# boardV4.net
KiCad netlist of a schematic drawn in EAGLE
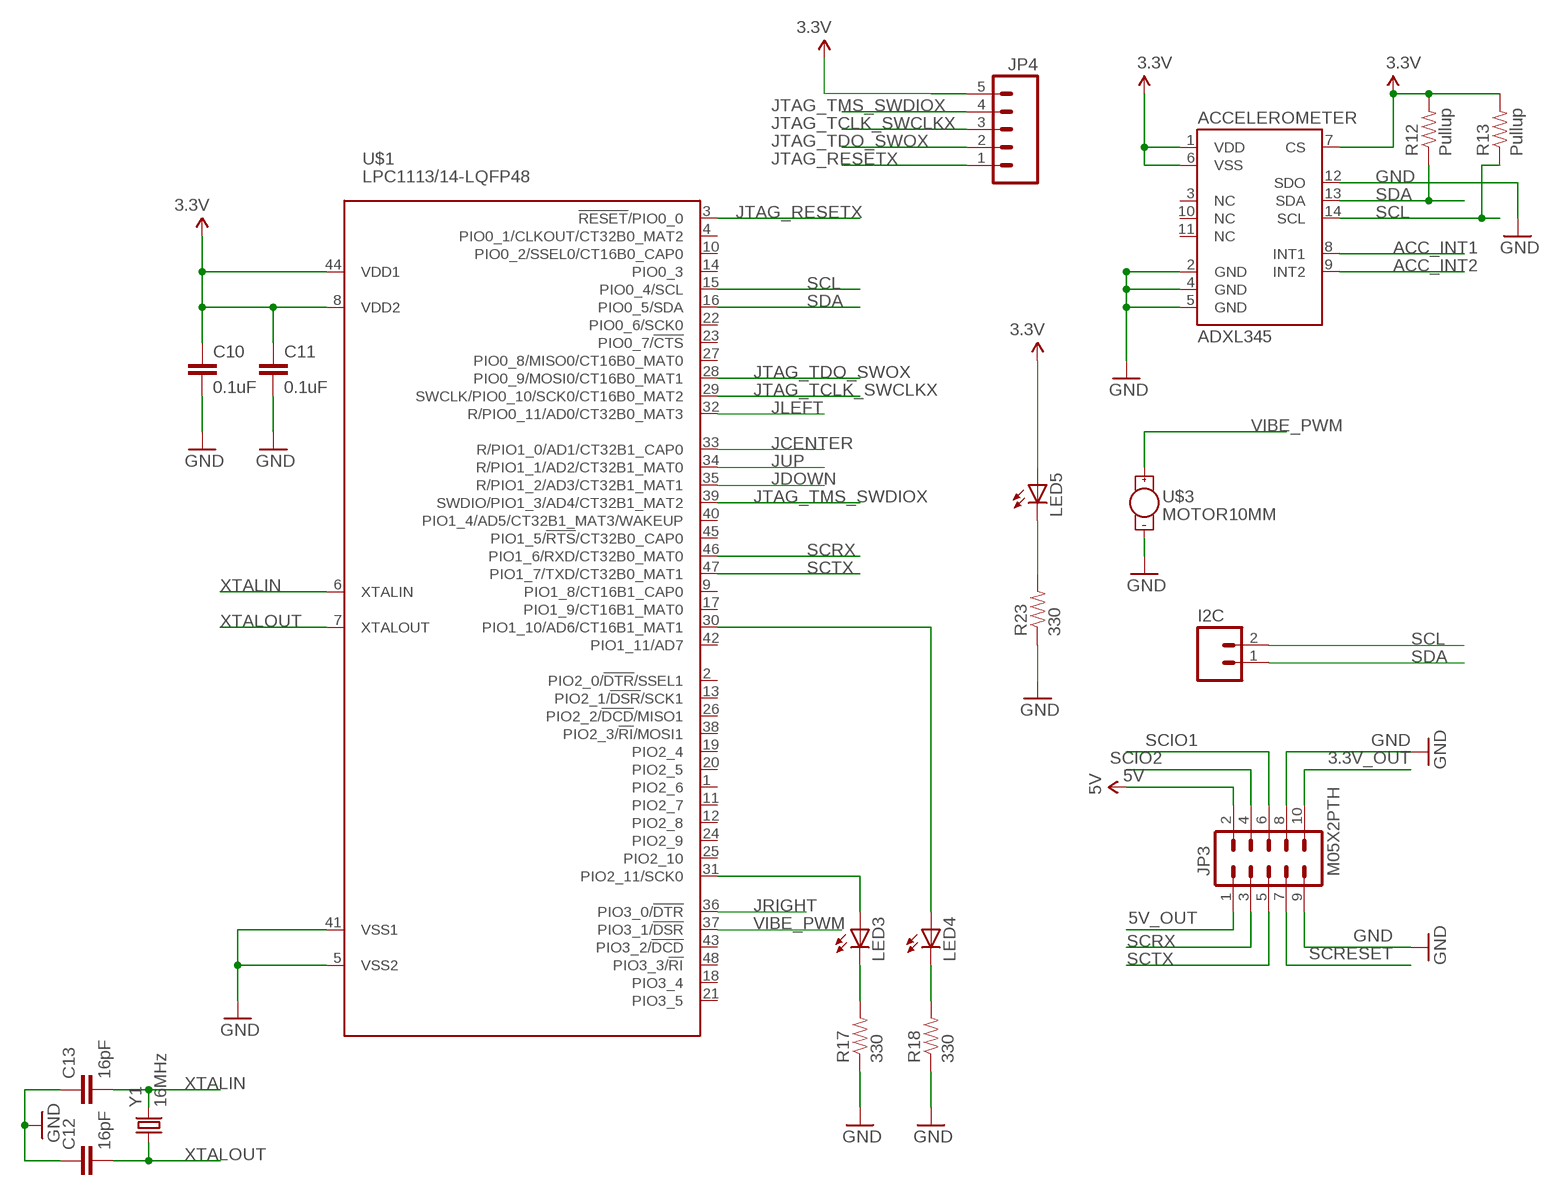
[diagram p0: schematic, sheet 1]
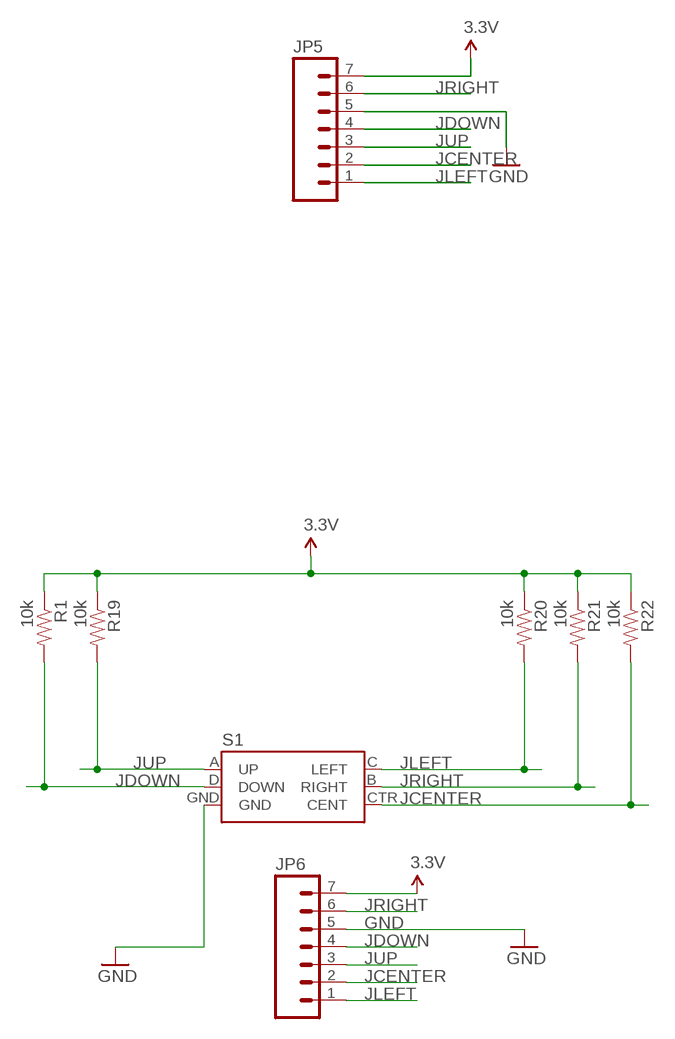
[diagram p1: schematic, sheet 2]
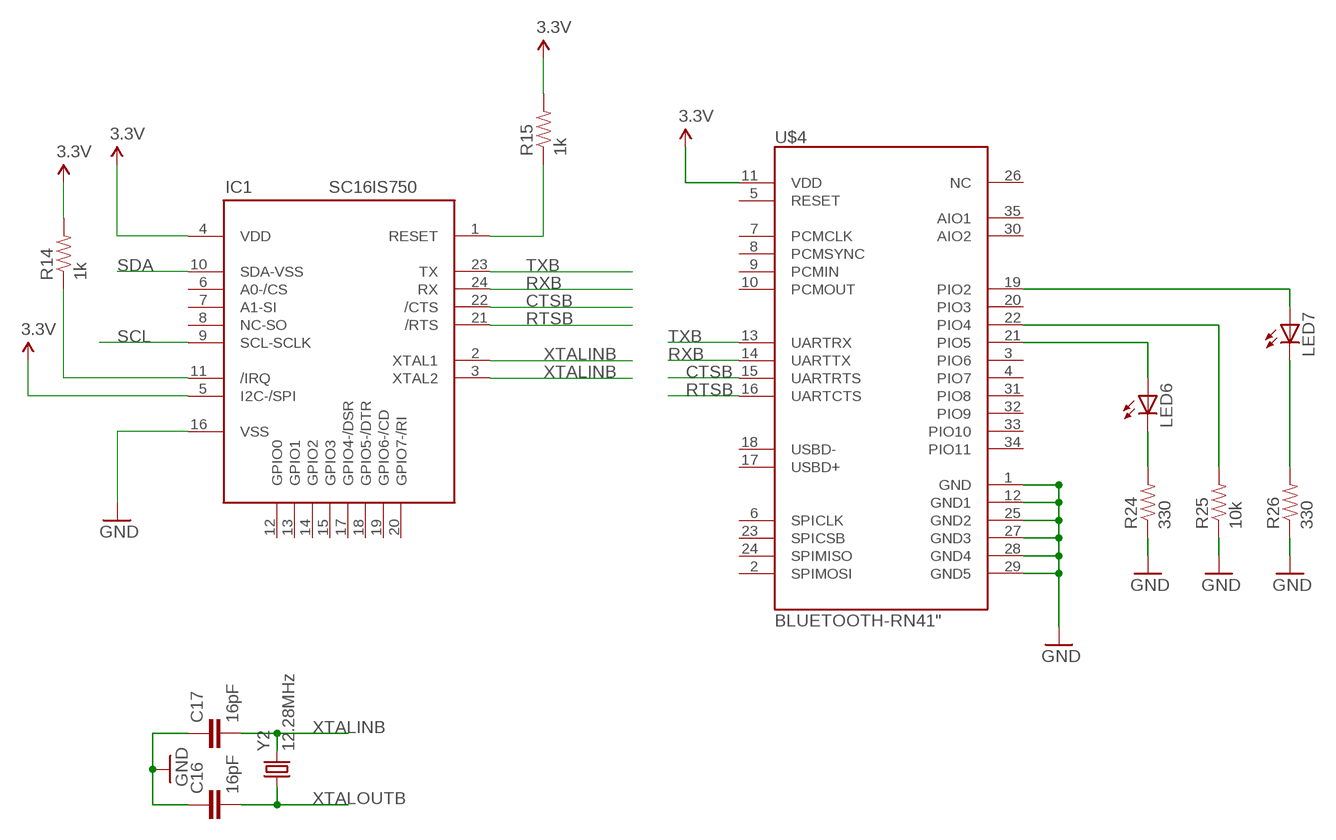
[diagram p2: schematic, sheet 3]
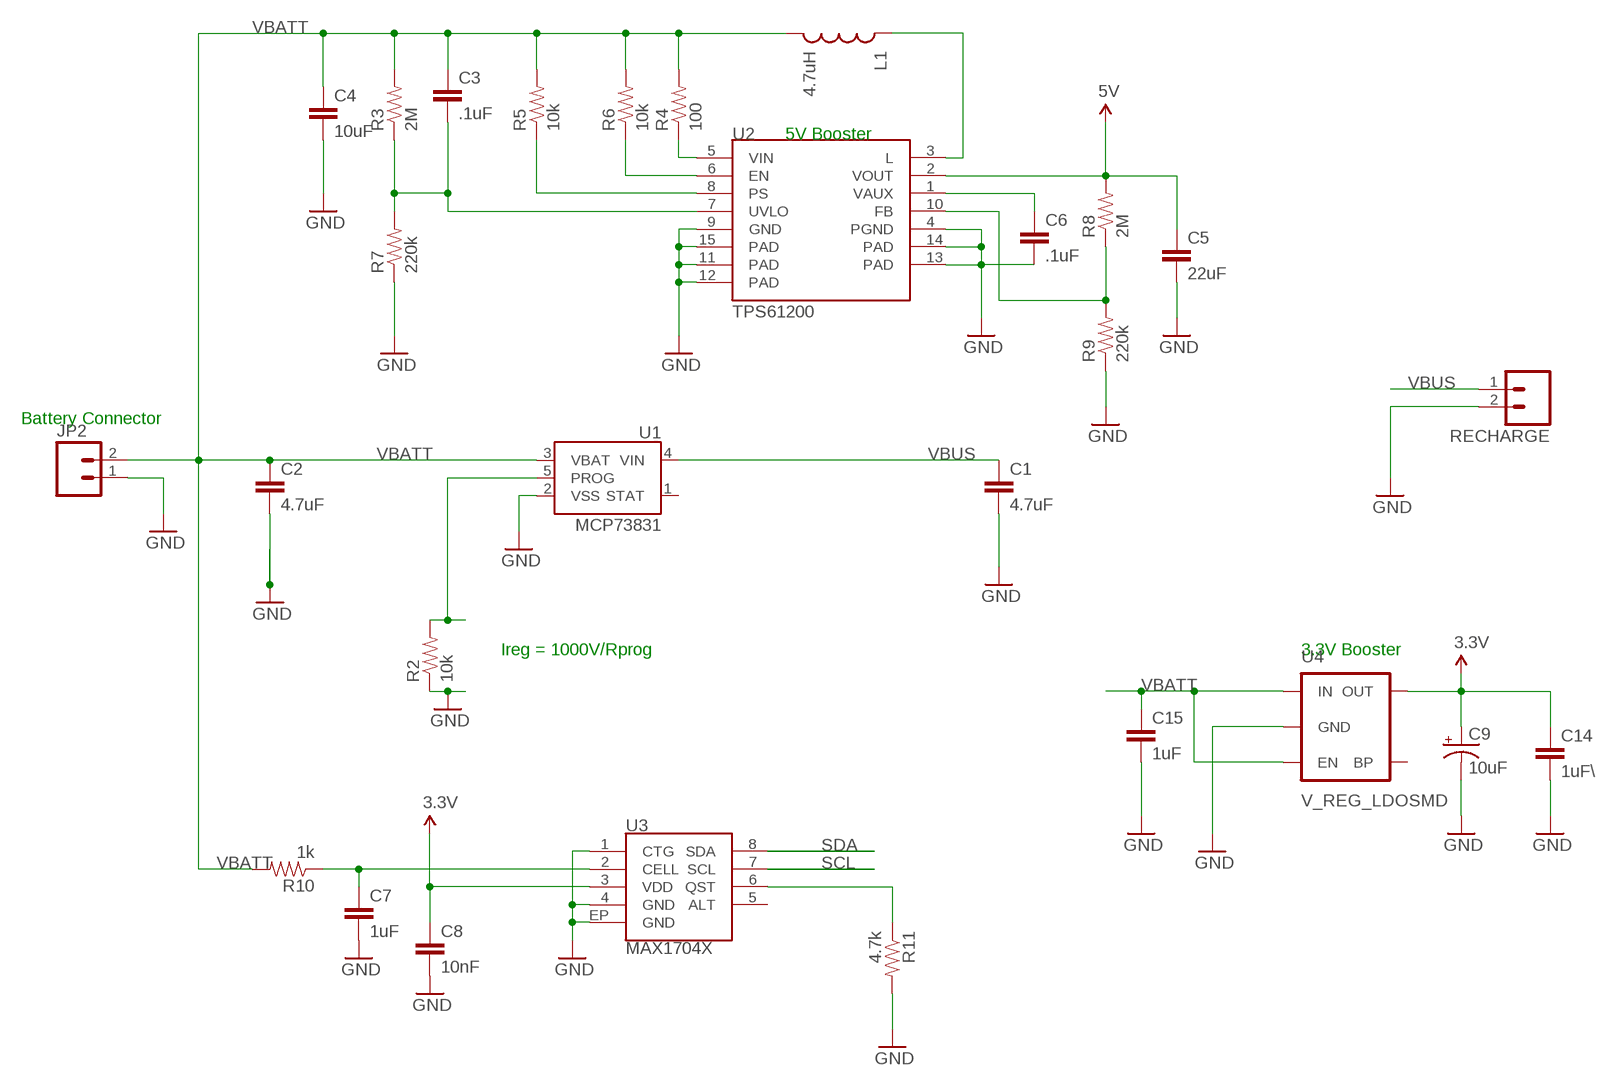
[diagram p3: schematic, sheet 4]

(export (version "E")
  (design (tool "Eeschema 10.0.6"))
  (components
    (comp (ref "C16")
      (value "16pF")
      (footprint "eagle-import:0603-CAP")
      (libsource (lib "eagle-import") (part "CAP0603-CAP"))
    )
    (comp (ref "C17")
      (value "16pF")
      (footprint "eagle-import:0603-CAP")
      (libsource (lib "eagle-import") (part "CAP0603-CAP"))
    )
    (comp (ref "IC1")
      (value "SC16IS750")
      (footprint "eagle-import:QFN-24")
      (libsource (lib "eagle-import") (part "SC16IS750"))
    )
    (comp (ref "LED6")
      (value "LED0603")
      (footprint "eagle-import:LED-0603")
      (libsource (lib "eagle-import") (part "LED0603"))
    )
    (comp (ref "LED7")
      (value "LED0603")
      (footprint "eagle-import:LED-0603")
      (libsource (lib "eagle-import") (part "LED0603"))
    )
    (comp (ref "R14")
      (value "1k")
      (footprint "eagle-import:0603-RES")
      (libsource (lib "eagle-import") (part "RESISTOR0603-RES"))
    )
    (comp (ref "R15")
      (value "1k")
      (footprint "eagle-import:0603-RES")
      (libsource (lib "eagle-import") (part "RESISTOR0603-RES"))
    )
    (comp (ref "R24")
      (value "330")
      (footprint "eagle-import:0603-RES")
      (libsource (lib "eagle-import") (part "RESISTOR0603-RES"))
    )
    (comp (ref "R25")
      (value "10k")
      (footprint "eagle-import:0603-RES")
      (libsource (lib "eagle-import") (part "RESISTOR0603-RES"))
    )
    (comp (ref "R26")
      (value "330")
      (footprint "eagle-import:0603-RES")
      (libsource (lib "eagle-import") (part "RESISTOR0603-RES"))
    )
    (comp (ref "U$4")
      (value "BLUETOOTH-RN41\"")
      (footprint "eagle-import:RN41")
      (libsource (lib "eagle-import") (part "BLUETOOTH-RN41{dblquote}"))
    )
    (comp (ref "Y2")
      (value "12.28MHz")
      (footprint "eagle-import:CRYSTAL-SMD-5X3")
      (libsource (lib "eagle-import") (part "CRYSTAL5X3"))
    )
    (comp (ref "JP5")
      (value "M07")
      (footprint "eagle-import:1X07")
      (libsource (lib "eagle-import") (part "M07"))
    )
    (comp (ref "JP6")
      (value "M07")
      (footprint "eagle-import:1X07")
      (libsource (lib "eagle-import") (part "M07"))
    )
    (comp (ref "R1")
      (value "10k")
      (footprint "eagle-import:0603-RES")
      (libsource (lib "eagle-import") (part "SparkFun-Resistors_RESISTOR0603-RES"))
    )
    (comp (ref "R19")
      (value "10k")
      (footprint "eagle-import:0603-RES")
      (libsource (lib "eagle-import") (part "SparkFun-Resistors_RESISTOR0603-RES"))
    )
    (comp (ref "R20")
      (value "10k")
      (footprint "eagle-import:0603-RES")
      (libsource (lib "eagle-import") (part "SparkFun-Resistors_RESISTOR0603-RES"))
    )
    (comp (ref "R21")
      (value "10k")
      (footprint "eagle-import:0603-RES")
      (libsource (lib "eagle-import") (part "SparkFun-Resistors_RESISTOR0603-RES"))
    )
    (comp (ref "R22")
      (value "10k")
      (footprint "eagle-import:0603-RES")
      (libsource (lib "eagle-import") (part "SparkFun-Resistors_RESISTOR0603-RES"))
    )
    (comp (ref "S1")
      (value "JOYSTICK_MINI")
      (footprint "eagle-import:JOYSTICK_MINI")
      (libsource (lib "eagle-import") (part "JOYSTICK_MINI"))
    )
    (comp (ref "C1")
      (value "4.7uF")
      (footprint "eagle-import:0603-CAP")
      (libsource (lib "eagle-import") (part "CAP0603-CAP"))
    )
    (comp (ref "C2")
      (value "4.7uF")
      (footprint "eagle-import:0603-CAP")
      (libsource (lib "eagle-import") (part "CAP0603-CAP"))
    )
    (comp (ref "C3")
      (value ".1uF")
      (footprint "eagle-import:0603-CAP")
      (libsource (lib "eagle-import") (part "CAP0603-CAP"))
    )
    (comp (ref "C4")
      (value "10uF")
      (footprint "eagle-import:0603-CAP")
      (libsource (lib "eagle-import") (part "CAP0603-CAP"))
    )
    (comp (ref "C5")
      (value "22uF")
      (footprint "eagle-import:0603-CAP")
      (libsource (lib "eagle-import") (part "CAP0603-CAP"))
    )
    (comp (ref "C6")
      (value ".1uF")
      (footprint "eagle-import:0603-CAP")
      (libsource (lib "eagle-import") (part "CAP0603-CAP"))
    )
    (comp (ref "C7")
      (value "1uF")
      (footprint "eagle-import:0603-CAP")
      (libsource (lib "eagle-import") (part "CAP0603-CAP"))
    )
    (comp (ref "C8")
      (value "10nF")
      (footprint "eagle-import:0603-CAP")
      (libsource (lib "eagle-import") (part "CAP0603-CAP"))
    )
    (comp (ref "C9")
      (value "10uF")
      (footprint "eagle-import:EIA3216")
      (libsource (lib "eagle-import") (part "10UF-TANT"))
    )
    (comp (ref "C14")
      (value "1uF\\")
      (footprint "eagle-import:0603-CAP")
      (libsource (lib "eagle-import") (part "CAP0603-CAP"))
    )
    (comp (ref "C15")
      (value "1uF")
      (footprint "eagle-import:0603-CAP")
      (libsource (lib "eagle-import") (part "CAP0603-CAP"))
    )
    (comp (ref "JP2")
      (value "M02PTH")
      (footprint "eagle-import:1X02")
      (libsource (lib "eagle-import") (part "M02PTH"))
    )
    (comp (ref "L1")
      (value "4.7uH")
      (footprint "eagle-import:CDRH2D09")
      (libsource (lib "eagle-import") (part "INDUCTOR."))
    )
    (comp (ref "R2")
      (value "10k")
      (footprint "eagle-import:0603-RES")
      (libsource (lib "eagle-import") (part "RESISTOR0603-RES"))
    )
    (comp (ref "R3")
      (value "2M")
      (footprint "eagle-import:0603-RES")
      (libsource (lib "eagle-import") (part "RESISTOR0603-RES"))
    )
    (comp (ref "R4")
      (value "100")
      (footprint "eagle-import:0603-RES")
      (libsource (lib "eagle-import") (part "RESISTOR0603-RES"))
    )
    (comp (ref "R5")
      (value "10k")
      (footprint "eagle-import:0603-RES")
      (libsource (lib "eagle-import") (part "RESISTOR0603-RES"))
    )
    (comp (ref "R6")
      (value "10k")
      (footprint "eagle-import:0603-RES")
      (libsource (lib "eagle-import") (part "RESISTOR0603-RES"))
    )
    (comp (ref "R7")
      (value "220k")
      (footprint "eagle-import:0603-RES")
      (libsource (lib "eagle-import") (part "RESISTOR0603-RES"))
    )
    (comp (ref "R8")
      (value "2M")
      (footprint "eagle-import:0603-RES")
      (libsource (lib "eagle-import") (part "SparkFun-Resistors_RESISTOR0603-RES"))
    )
    (comp (ref "R9")
      (value "220k")
      (footprint "eagle-import:0603-RES")
      (libsource (lib "eagle-import") (part "SparkFun-Resistors_RESISTOR0603-RES"))
    )
    (comp (ref "R10")
      (value "1k")
      (footprint "eagle-import:0603-RES")
      (libsource (lib "eagle-import") (part "RESISTOR0603-RES"))
    )
    (comp (ref "R11")
      (value "4.7k")
      (footprint "eagle-import:0603-RES")
      (libsource (lib "eagle-import") (part "RESISTOR0603-RES"))
    )
    (comp (ref "RECHARGE")
      (value "M02POLAR")
      (footprint "eagle-import:MOLEX-1X2")
      (libsource (lib "eagle-import") (part "M02POLAR"))
    )
    (comp (ref "U1")
      (value "MCP73831")
      (footprint "eagle-import:SOT23-5")
      (libsource (lib "eagle-import") (part "MCP73831"))
    )
    (comp (ref "U2")
      (value "TPS61200")
      (footprint "eagle-import:QFN-10_PAD")
      (libsource (lib "eagle-import") (part "TPS61200"))
    )
    (comp (ref "U3")
      (value "MAX1704X")
      (footprint "eagle-import:TDFN-8")
      (libsource (lib "eagle-import") (part "MAX1704X"))
    )
    (comp (ref "U4")
      (value "V_REG_LDOSMD")
      (footprint "eagle-import:SOT23-5")
      (libsource (lib "eagle-import") (part "V_REG_LDOSMD"))
    )
    (comp (ref "ACCELEROMETER")
      (value "ADXL345")
      (footprint "eagle-import:LGA14")
      (libsource (lib "eagle-import") (part "ADXL345"))
    )
    (comp (ref "C10")
      (value "0.1uF")
      (footprint "eagle-import:0603-CAP")
      (libsource (lib "eagle-import") (part "CAP0603-CAP"))
    )
    (comp (ref "C11")
      (value "0.1uF")
      (footprint "eagle-import:0603-CAP")
      (libsource (lib "eagle-import") (part "CAP0603-CAP"))
    )
    (comp (ref "C12")
      (value "16pF")
      (footprint "eagle-import:0603-CAP")
      (libsource (lib "eagle-import") (part "CAP0603-CAP"))
    )
    (comp (ref "C13")
      (value "16pF")
      (footprint "eagle-import:0603-CAP")
      (libsource (lib "eagle-import") (part "CAP0603-CAP"))
    )
    (comp (ref "I2C")
      (value "M02POLAR")
      (footprint "eagle-import:MOLEX-1X2")
      (libsource (lib "eagle-import") (part "M02POLAR"))
    )
    (comp (ref "JP3")
      (value "M05X2PTH")
      (footprint "eagle-import:AVR_ICSP")
      (libsource (lib "eagle-import") (part "M05X2PTH"))
    )
    (comp (ref "JP4")
      (value "M05PTH")
      (footprint "eagle-import:1X05")
      (libsource (lib "eagle-import") (part "M05PTH"))
    )
    (comp (ref "LED3")
      (value "LED0603")
      (footprint "eagle-import:LED-0603")
      (libsource (lib "eagle-import") (part "LED0603"))
    )
    (comp (ref "LED4")
      (value "LED0603")
      (footprint "eagle-import:LED-0603")
      (libsource (lib "eagle-import") (part "LED0603"))
    )
    (comp (ref "LED5")
      (value "LED0603")
      (footprint "eagle-import:LED-0603")
      (libsource (lib "eagle-import") (part "LED0603"))
    )
    (comp (ref "R12")
      (value "Pullup")
      (footprint "eagle-import:0603-RES")
      (libsource (lib "eagle-import") (part "SparkFun-Resistors_RESISTOR0603-RES"))
    )
    (comp (ref "R13")
      (value "Pullup")
      (footprint "eagle-import:0603-RES")
      (libsource (lib "eagle-import") (part "SparkFun-Resistors_RESISTOR0603-RES"))
    )
    (comp (ref "R17")
      (value "330")
      (footprint "eagle-import:0603-RES")
      (libsource (lib "eagle-import") (part "RESISTOR0603-RES"))
    )
    (comp (ref "R18")
      (value "330")
      (footprint "eagle-import:0603-RES")
      (libsource (lib "eagle-import") (part "RESISTOR0603-RES"))
    )
    (comp (ref "R23")
      (value "330")
      (footprint "eagle-import:0603-RES")
      (libsource (lib "eagle-import") (part "RESISTOR0603-RES"))
    )
    (comp (ref "U$1")
      (value "LPC1113/14-LQFP48")
      (footprint "eagle-import:LQFP48")
      (libsource (lib "eagle-import") (part "LPC1113/14-LQFP48"))
    )
    (comp (ref "U$3")
      (value "MOTOR10MM")
      (footprint "eagle-import:VIBE-MOTOR-10MM")
      (libsource (lib "eagle-import") (part "MOTOR10MM"))
    )
    (comp (ref "Y1")
      (value "16MHz")
      (footprint "eagle-import:CRYSTAL-SMD-5X3")
      (libsource (lib "eagle-import") (part "CRYSTAL5X3"))
    )
  )
  (nets
    (net (code "1") (name "3.3V") (class "Default")
      (node (ref "ACCELEROMETER") (pin "1") (pinfunction "VDD_1") (pintype "bidirectional"))
      (node (ref "ACCELEROMETER") (pin "6") (pinfunction "VSS_6") (pintype "bidirectional"))
      (node (ref "ACCELEROMETER") (pin "7") (pinfunction "CS_7") (pintype "bidirectional"))
      (node (ref "C10") (pin "1") (pinfunction "1_1") (pintype "passive"))
      (node (ref "C11") (pin "1") (pinfunction "1_1") (pintype "passive"))
      (node (ref "C14") (pin "1") (pinfunction "1_1") (pintype "passive"))
      (node (ref "C8") (pin "1") (pinfunction "1_1") (pintype "passive"))
      (node (ref "C9") (pin "A") (pinfunction "+_A") (pintype "passive"))
      (node (ref "IC1") (pin "4") (pinfunction "VDD_4") (pintype "bidirectional"))
      (node (ref "IC1") (pin "5") (pinfunction "I2C-/SPI_5") (pintype "bidirectional"))
      (node (ref "JP4") (pin "5") (pinfunction "5_5") (pintype "passive"))
      (node (ref "JP5") (pin "7") (pinfunction "7_7") (pintype "passive"))
      (node (ref "JP6") (pin "7") (pinfunction "7_7") (pintype "passive"))
      (node (ref "LED5") (pin "A") (pinfunction "A_A") (pintype "passive"))
      (node (ref "R1") (pin "1") (pinfunction "1_1") (pintype "passive"))
      (node (ref "R12") (pin "2") (pinfunction "2_2") (pintype "passive"))
      (node (ref "R13") (pin "2") (pinfunction "2_2") (pintype "passive"))
      (node (ref "R14") (pin "2") (pinfunction "2_2") (pintype "passive"))
      (node (ref "R15") (pin "2") (pinfunction "2_2") (pintype "passive"))
      (node (ref "R19") (pin "1") (pinfunction "1_1") (pintype "passive"))
      (node (ref "R20") (pin "1") (pinfunction "1_1") (pintype "passive"))
      (node (ref "R21") (pin "1") (pinfunction "1_1") (pintype "passive"))
      (node (ref "R22") (pin "1") (pinfunction "1_1") (pintype "passive"))
      (node (ref "U$1") (pin "44") (pinfunction "VDD1_44") (pintype "power_in"))
      (node (ref "U$1") (pin "8") (pinfunction "VDD2_8") (pintype "power_in"))
      (node (ref "U$4") (pin "11") (pinfunction "VDD_11") (pintype "bidirectional"))
      (node (ref "U3") (pin "3") (pinfunction "VDD_3") (pintype "bidirectional"))
      (node (ref "U4") (pin "5") (pinfunction "OUT_5") (pintype "passive"))
    )
    (net (code "2") (name "3.3V_OUT") (class "Default")
      (node (ref "JP3") (pin "10") (pinfunction "10_10") (pintype "passive"))
    )
    (net (code "3") (name "5V") (class "Default")
      (node (ref "C5") (pin "1") (pinfunction "1_1") (pintype "passive"))
      (node (ref "JP3") (pin "2") (pinfunction "2_2") (pintype "passive"))
      (node (ref "R8") (pin "2") (pinfunction "2_2") (pintype "passive"))
      (node (ref "U2") (pin "2") (pinfunction "VOUT_2") (pintype "passive"))
    )
    (net (code "4") (name "5V_OUT") (class "Default")
      (node (ref "JP3") (pin "1") (pinfunction "1_1") (pintype "passive"))
    )
    (net (code "5") (name "ACC_INT1") (class "Default")
      (node (ref "ACCELEROMETER") (pin "8") (pinfunction "INT1_8") (pintype "bidirectional"))
    )
    (net (code "6") (name "ACC_INT2") (class "Default")
      (node (ref "ACCELEROMETER") (pin "9") (pinfunction "INT2_9") (pintype "bidirectional"))
    )
    (net (code "7") (name "CTSB") (class "Default")
      (node (ref "IC1") (pin "22") (pinfunction "/CTS_22") (pintype "bidirectional"))
      (node (ref "U$4") (pin "15") (pinfunction "UARTRTS_15") (pintype "bidirectional"))
    )
    (net (code "8") (name "GND") (class "Default")
      (node (ref "ACCELEROMETER") (pin "12") (pinfunction "SDO_12") (pintype "bidirectional"))
      (node (ref "ACCELEROMETER") (pin "2") (pinfunction "GND_2") (pintype "bidirectional"))
      (node (ref "ACCELEROMETER") (pin "4") (pinfunction "GND_4") (pintype "bidirectional"))
      (node (ref "ACCELEROMETER") (pin "5") (pinfunction "GND_5") (pintype "bidirectional"))
      (node (ref "C1") (pin "2") (pinfunction "2_2") (pintype "passive"))
      (node (ref "C10") (pin "2") (pinfunction "2_2") (pintype "passive"))
      (node (ref "C11") (pin "2") (pinfunction "2_2") (pintype "passive"))
      (node (ref "C12") (pin "1") (pinfunction "1_1") (pintype "passive"))
      (node (ref "C13") (pin "1") (pinfunction "1_1") (pintype "passive"))
      (node (ref "C14") (pin "2") (pinfunction "2_2") (pintype "passive"))
      (node (ref "C15") (pin "2") (pinfunction "2_2") (pintype "passive"))
      (node (ref "C16") (pin "1") (pinfunction "1_1") (pintype "passive"))
      (node (ref "C17") (pin "1") (pinfunction "1_1") (pintype "passive"))
      (node (ref "C2") (pin "2") (pinfunction "2_2") (pintype "passive"))
      (node (ref "C4") (pin "2") (pinfunction "2_2") (pintype "passive"))
      (node (ref "C5") (pin "2") (pinfunction "2_2") (pintype "passive"))
      (node (ref "C6") (pin "2") (pinfunction "2_2") (pintype "passive"))
      (node (ref "C7") (pin "2") (pinfunction "2_2") (pintype "passive"))
      (node (ref "C8") (pin "2") (pinfunction "2_2") (pintype "passive"))
      (node (ref "C9") (pin "C") (pinfunction "-_C") (pintype "passive"))
      (node (ref "IC1") (pin "16") (pinfunction "VSS_16") (pintype "bidirectional"))
      (node (ref "JP2") (pin "1") (pinfunction "1_1") (pintype "passive"))
      (node (ref "JP3") (pin "8") (pinfunction "8_8") (pintype "passive"))
      (node (ref "JP3") (pin "9") (pinfunction "9_9") (pintype "passive"))
      (node (ref "JP5") (pin "5") (pinfunction "5_5") (pintype "passive"))
      (node (ref "JP6") (pin "5") (pinfunction "5_5") (pintype "passive"))
      (node (ref "R11") (pin "2") (pinfunction "2_2") (pintype "passive"))
      (node (ref "R17") (pin "1") (pinfunction "1_1") (pintype "passive"))
      (node (ref "R18") (pin "1") (pinfunction "1_1") (pintype "passive"))
      (node (ref "R2") (pin "1") (pinfunction "1_1") (pintype "passive"))
      (node (ref "R23") (pin "1") (pinfunction "1_1") (pintype "passive"))
      (node (ref "R24") (pin "1") (pinfunction "1_1") (pintype "passive"))
      (node (ref "R25") (pin "1") (pinfunction "1_1") (pintype "passive"))
      (node (ref "R26") (pin "1") (pinfunction "1_1") (pintype "passive"))
      (node (ref "R7") (pin "1") (pinfunction "1_1") (pintype "passive"))
      (node (ref "R9") (pin "1") (pinfunction "1_1") (pintype "passive"))
      (node (ref "RECHARGE") (pin "2") (pinfunction "2_2") (pintype "passive"))
      (node (ref "S1") (pin "GND") (pinfunction "GND_GND") (pintype "bidirectional"))
      (node (ref "U$1") (pin "41") (pinfunction "VSS1_41") (pintype "power_in"))
      (node (ref "U$1") (pin "5") (pinfunction "VSS2_5") (pintype "power_in"))
      (node (ref "U$3") (pin "-") (pinfunction "-_-") (pintype "bidirectional"))
      (node (ref "U$4") (pin "1") (pinfunction "GND_1") (pintype "bidirectional"))
      (node (ref "U$4") (pin "12") (pinfunction "GND1_12") (pintype "bidirectional"))
      (node (ref "U$4") (pin "25") (pinfunction "GND2_25") (pintype "bidirectional"))
      (node (ref "U$4") (pin "27") (pinfunction "GND3_27") (pintype "bidirectional"))
      (node (ref "U$4") (pin "28") (pinfunction "GND4_28") (pintype "bidirectional"))
      (node (ref "U$4") (pin "29") (pinfunction "GND5_29") (pintype "bidirectional"))
      (node (ref "U1") (pin "2") (pinfunction "VSS_2") (pintype "power_in"))
      (node (ref "U2") (pin "11") (pinfunction "PAD_11") (pintype "power_in"))
      (node (ref "U2") (pin "12") (pinfunction "PAD_12") (pintype "power_in"))
      (node (ref "U2") (pin "13") (pinfunction "PAD_13") (pintype "power_in"))
      (node (ref "U2") (pin "14") (pinfunction "PAD_14") (pintype "power_in"))
      (node (ref "U2") (pin "15") (pinfunction "PAD_15") (pintype "power_in"))
      (node (ref "U2") (pin "4") (pinfunction "PGND_4") (pintype "power_in"))
      (node (ref "U2") (pin "9") (pinfunction "GND_9") (pintype "power_in"))
      (node (ref "U3") (pin "1") (pinfunction "CTG_1") (pintype "bidirectional"))
      (node (ref "U3") (pin "4") (pinfunction "GND_4") (pintype "bidirectional"))
      (node (ref "U3") (pin "EP") (pinfunction "GND_EP") (pintype "bidirectional"))
      (node (ref "U4") (pin "2") (pinfunction "GND_2") (pintype "input"))
    )
    (net (code "9") (name "JCENTER") (class "Default")
      (node (ref "JP5") (pin "2") (pinfunction "2_2") (pintype "passive"))
      (node (ref "JP6") (pin "2") (pinfunction "2_2") (pintype "passive"))
      (node (ref "R22") (pin "2") (pinfunction "2_2") (pintype "passive"))
      (node (ref "S1") (pin "CTR") (pinfunction "CENT_CTR") (pintype "bidirectional"))
      (node (ref "U$1") (pin "33") (pinfunction "R/PIO1_0/AD1/CT32B1_CAP0_33") (pintype "bidirectional"))
    )
    (net (code "10") (name "JDOWN") (class "Default")
      (node (ref "JP5") (pin "4") (pinfunction "4_4") (pintype "passive"))
      (node (ref "JP6") (pin "4") (pinfunction "4_4") (pintype "passive"))
      (node (ref "R1") (pin "2") (pinfunction "2_2") (pintype "passive"))
      (node (ref "S1") (pin "D") (pinfunction "DOWN_D") (pintype "bidirectional"))
      (node (ref "U$1") (pin "35") (pinfunction "R/PIO1_2/AD3/CT32B1_MAT1_35") (pintype "bidirectional"))
    )
    (net (code "11") (name "JLEFT") (class "Default")
      (node (ref "JP5") (pin "1") (pinfunction "1_1") (pintype "passive"))
      (node (ref "JP6") (pin "1") (pinfunction "1_1") (pintype "passive"))
      (node (ref "R20") (pin "2") (pinfunction "2_2") (pintype "passive"))
      (node (ref "S1") (pin "C") (pinfunction "LEFT_C") (pintype "bidirectional"))
      (node (ref "U$1") (pin "32") (pinfunction "R/PIO0_11/AD0/CT32B0_MAT3_32") (pintype "bidirectional"))
    )
    (net (code "12") (name "JRIGHT") (class "Default")
      (node (ref "JP5") (pin "6") (pinfunction "6_6") (pintype "passive"))
      (node (ref "JP6") (pin "6") (pinfunction "6_6") (pintype "passive"))
      (node (ref "R21") (pin "2") (pinfunction "2_2") (pintype "passive"))
      (node (ref "S1") (pin "B") (pinfunction "RIGHT_B") (pintype "bidirectional"))
      (node (ref "U$1") (pin "36") (pinfunction "PIO3_0/~{DTR}_36") (pintype "bidirectional"))
    )
    (net (code "13") (name "JTAG_RESETX") (class "Default")
      (node (ref "JP4") (pin "1") (pinfunction "1_1") (pintype "passive"))
      (node (ref "U$1") (pin "3") (pinfunction "~{RESET}/PIO0_0_3") (pintype "bidirectional"))
    )
    (net (code "14") (name "JTAG_TCLK_SWCLKX") (class "Default")
      (node (ref "JP4") (pin "3") (pinfunction "3_3") (pintype "passive"))
      (node (ref "U$1") (pin "29") (pinfunction "SWCLK/PIO0_10/SCK0/CT16B0_MAT2_29") (pintype "bidirectional"))
    )
    (net (code "15") (name "JTAG_TDO_SWOX") (class "Default")
      (node (ref "JP4") (pin "2") (pinfunction "2_2") (pintype "passive"))
      (node (ref "U$1") (pin "28") (pinfunction "PIO0_9/MOSI0/CT16B0_MAT1_28") (pintype "bidirectional"))
    )
    (net (code "16") (name "JTAG_TMS_SWDIOX") (class "Default")
      (node (ref "JP4") (pin "4") (pinfunction "4_4") (pintype "passive"))
      (node (ref "U$1") (pin "39") (pinfunction "SWDIO/PIO1_3/AD4/CT32B1_MAT2_39") (pintype "bidirectional"))
    )
    (net (code "17") (name "JUP") (class "Default")
      (node (ref "JP5") (pin "3") (pinfunction "3_3") (pintype "passive"))
      (node (ref "JP6") (pin "3") (pinfunction "3_3") (pintype "passive"))
      (node (ref "R19") (pin "2") (pinfunction "2_2") (pintype "passive"))
      (node (ref "S1") (pin "A") (pinfunction "UP_A") (pintype "bidirectional"))
      (node (ref "U$1") (pin "34") (pinfunction "R/PIO1_1/AD2/CT32B1_MAT0_34") (pintype "bidirectional"))
    )
    (net (code "18") (name "Net-(IC1-RESET)") (class "Default")
      (node (ref "IC1") (pin "1") (pinfunction "RESET_1") (pintype "bidirectional"))
      (node (ref "R15") (pin "1") (pinfunction "1_1") (pintype "passive"))
    )
    (net (code "19") (name "Net-(IC1-{slash}IRQ)") (class "Default")
      (node (ref "IC1") (pin "11") (pinfunction "/IRQ_11") (pintype "bidirectional"))
      (node (ref "R14") (pin "1") (pinfunction "1_1") (pintype "passive"))
    )
    (net (code "20") (name "Net-(L1-1)") (class "Default")
      (node (ref "L1") (pin "P$1") (pinfunction "1_P$1") (pintype "passive"))
      (node (ref "U2") (pin "3") (pinfunction "L_3") (pintype "passive"))
    )
    (net (code "21") (name "Net-(LED3-PadC)") (class "Default")
      (node (ref "LED3") (pin "C") (pinfunction "C_C") (pintype "passive"))
      (node (ref "R17") (pin "2") (pinfunction "2_2") (pintype "passive"))
    )
    (net (code "22") (name "Net-(LED4-PadC)") (class "Default")
      (node (ref "LED4") (pin "C") (pinfunction "C_C") (pintype "passive"))
      (node (ref "R18") (pin "2") (pinfunction "2_2") (pintype "passive"))
    )
    (net (code "23") (name "Net-(LED5-PadC)") (class "Default")
      (node (ref "LED5") (pin "C") (pinfunction "C_C") (pintype "passive"))
      (node (ref "R23") (pin "2") (pinfunction "2_2") (pintype "passive"))
    )
    (net (code "24") (name "Net-(LED6-PadC)") (class "Default")
      (node (ref "LED6") (pin "C") (pinfunction "C_C") (pintype "passive"))
      (node (ref "R24") (pin "2") (pinfunction "2_2") (pintype "passive"))
    )
    (net (code "25") (name "Net-(LED7-PadC)") (class "Default")
      (node (ref "LED7") (pin "C") (pinfunction "C_C") (pintype "passive"))
      (node (ref "R26") (pin "2") (pinfunction "2_2") (pintype "passive"))
    )
    (net (code "26") (name "Net-(U$1-PIO1_10{slash}AD6{slash}CT16B1_MAT1)") (class "Default")
      (node (ref "LED4") (pin "A") (pinfunction "A_A") (pintype "passive"))
      (node (ref "U$1") (pin "30") (pinfunction "PIO1_10/AD6/CT16B1_MAT1_30") (pintype "bidirectional"))
    )
    (net (code "27") (name "Net-(U$1-PIO2_11{slash}SCK0)") (class "Default")
      (node (ref "LED3") (pin "A") (pinfunction "A_A") (pintype "passive"))
      (node (ref "U$1") (pin "31") (pinfunction "PIO2_11/SCK0_31") (pintype "bidirectional"))
    )
    (net (code "28") (name "Net-(U$4-PIO2)") (class "Default")
      (node (ref "LED7") (pin "A") (pinfunction "A_A") (pintype "passive"))
      (node (ref "U$4") (pin "19") (pinfunction "PIO2_19") (pintype "bidirectional"))
    )
    (net (code "29") (name "Net-(U$4-PIO4)") (class "Default")
      (node (ref "R25") (pin "2") (pinfunction "2_2") (pintype "passive"))
      (node (ref "U$4") (pin "22") (pinfunction "PIO4_22") (pintype "bidirectional"))
    )
    (net (code "30") (name "Net-(U$4-PIO5)") (class "Default")
      (node (ref "LED6") (pin "A") (pinfunction "A_A") (pintype "passive"))
      (node (ref "U$4") (pin "21") (pinfunction "PIO5_21") (pintype "bidirectional"))
    )
    (net (code "31") (name "Net-(U1-PROG)") (class "Default")
      (node (ref "R2") (pin "2") (pinfunction "2_2") (pintype "passive"))
      (node (ref "U1") (pin "5") (pinfunction "PROG_5") (pintype "input"))
    )
    (net (code "32") (name "Net-(U2-EN)") (class "Default")
      (node (ref "R6") (pin "1") (pinfunction "1_1") (pintype "passive"))
      (node (ref "U2") (pin "6") (pinfunction "EN_6") (pintype "input"))
    )
    (net (code "33") (name "Net-(U2-FB)") (class "Default")
      (node (ref "R8") (pin "1") (pinfunction "1_1") (pintype "passive"))
      (node (ref "R9") (pin "2") (pinfunction "2_2") (pintype "passive"))
      (node (ref "U2") (pin "10") (pinfunction "FB_10") (pintype "passive"))
    )
    (net (code "34") (name "Net-(U2-PS)") (class "Default")
      (node (ref "R5") (pin "1") (pinfunction "1_1") (pintype "passive"))
      (node (ref "U2") (pin "8") (pinfunction "PS_8") (pintype "input"))
    )
    (net (code "35") (name "Net-(U2-UVLO)") (class "Default")
      (node (ref "C3") (pin "2") (pinfunction "2_2") (pintype "passive"))
      (node (ref "R3") (pin "1") (pinfunction "1_1") (pintype "passive"))
      (node (ref "R7") (pin "2") (pinfunction "2_2") (pintype "passive"))
      (node (ref "U2") (pin "7") (pinfunction "UVLO_7") (pintype "passive"))
    )
    (net (code "36") (name "Net-(U2-VAUX)") (class "Default")
      (node (ref "C6") (pin "1") (pinfunction "1_1") (pintype "passive"))
      (node (ref "U2") (pin "1") (pinfunction "VAUX_1") (pintype "passive"))
    )
    (net (code "37") (name "Net-(U2-VIN)") (class "Default")
      (node (ref "R4") (pin "1") (pinfunction "1_1") (pintype "passive"))
      (node (ref "U2") (pin "5") (pinfunction "VIN_5") (pintype "power_in"))
    )
    (net (code "38") (name "Net-(U3-CELL)") (class "Default")
      (node (ref "C7") (pin "1") (pinfunction "1_1") (pintype "passive"))
      (node (ref "R10") (pin "1") (pinfunction "1_1") (pintype "passive"))
      (node (ref "U3") (pin "2") (pinfunction "CELL_2") (pintype "bidirectional"))
    )
    (net (code "39") (name "Net-(U3-QST)") (class "Default")
      (node (ref "R11") (pin "1") (pinfunction "1_1") (pintype "passive"))
      (node (ref "U3") (pin "6") (pinfunction "QST_6") (pintype "bidirectional"))
    )
    (net (code "40") (name "RTSB") (class "Default")
      (node (ref "IC1") (pin "21") (pinfunction "/RTS_21") (pintype "bidirectional"))
      (node (ref "U$4") (pin "16") (pinfunction "UARTCTS_16") (pintype "bidirectional"))
    )
    (net (code "41") (name "RXB") (class "Default")
      (node (ref "IC1") (pin "24") (pinfunction "RX_24") (pintype "bidirectional"))
      (node (ref "U$4") (pin "14") (pinfunction "UARTTX_14") (pintype "bidirectional"))
    )
    (net (code "42") (name "SCIO1") (class "Default")
      (node (ref "JP3") (pin "6") (pinfunction "6_6") (pintype "passive"))
    )
    (net (code "43") (name "SCIO2") (class "Default")
      (node (ref "JP3") (pin "4") (pinfunction "4_4") (pintype "passive"))
    )
    (net (code "44") (name "SCL") (class "Default")
      (node (ref "ACCELEROMETER") (pin "14") (pinfunction "SCL_14") (pintype "bidirectional"))
      (node (ref "I2C") (pin "2") (pinfunction "2_2") (pintype "passive"))
      (node (ref "IC1") (pin "9") (pinfunction "SCL-SCLK_9") (pintype "bidirectional"))
      (node (ref "R13") (pin "1") (pinfunction "1_1") (pintype "passive"))
      (node (ref "U$1") (pin "15") (pinfunction "PIO0_4/SCL_15") (pintype "bidirectional"))
      (node (ref "U3") (pin "7") (pinfunction "SCL_7") (pintype "bidirectional"))
    )
    (net (code "45") (name "SCRESET") (class "Default")
      (node (ref "JP3") (pin "7") (pinfunction "7_7") (pintype "passive"))
    )
    (net (code "46") (name "SCRX") (class "Default")
      (node (ref "JP3") (pin "3") (pinfunction "3_3") (pintype "passive"))
      (node (ref "U$1") (pin "46") (pinfunction "PIO1_6/RXD/CT32B0_MAT0_46") (pintype "bidirectional"))
    )
    (net (code "47") (name "SCTX") (class "Default")
      (node (ref "JP3") (pin "5") (pinfunction "5_5") (pintype "passive"))
      (node (ref "U$1") (pin "47") (pinfunction "PIO1_7/TXD/CT32B0_MAT1_47") (pintype "bidirectional"))
    )
    (net (code "48") (name "SDA") (class "Default")
      (node (ref "ACCELEROMETER") (pin "13") (pinfunction "SDA_13") (pintype "bidirectional"))
      (node (ref "I2C") (pin "1") (pinfunction "1_1") (pintype "passive"))
      (node (ref "IC1") (pin "10") (pinfunction "SDA-VSS_10") (pintype "bidirectional"))
      (node (ref "R12") (pin "1") (pinfunction "1_1") (pintype "passive"))
      (node (ref "U$1") (pin "16") (pinfunction "PIO0_5/SDA_16") (pintype "bidirectional"))
      (node (ref "U3") (pin "8") (pinfunction "SDA_8") (pintype "bidirectional"))
    )
    (net (code "49") (name "TXB") (class "Default")
      (node (ref "IC1") (pin "23") (pinfunction "TX_23") (pintype "bidirectional"))
      (node (ref "U$4") (pin "13") (pinfunction "UARTRX_13") (pintype "bidirectional"))
    )
    (net (code "50") (name "VBATT") (class "Default")
      (node (ref "C15") (pin "1") (pinfunction "1_1") (pintype "passive"))
      (node (ref "C2") (pin "1") (pinfunction "1_1") (pintype "passive"))
      (node (ref "C3") (pin "1") (pinfunction "1_1") (pintype "passive"))
      (node (ref "C4") (pin "1") (pinfunction "1_1") (pintype "passive"))
      (node (ref "JP2") (pin "2") (pinfunction "2_2") (pintype "passive"))
      (node (ref "L1") (pin "P$2") (pinfunction "2_P$2") (pintype "passive"))
      (node (ref "R10") (pin "2") (pinfunction "2_2") (pintype "passive"))
      (node (ref "R3") (pin "2") (pinfunction "2_2") (pintype "passive"))
      (node (ref "R4") (pin "2") (pinfunction "2_2") (pintype "passive"))
      (node (ref "R5") (pin "2") (pinfunction "2_2") (pintype "passive"))
      (node (ref "R6") (pin "2") (pinfunction "2_2") (pintype "passive"))
      (node (ref "U1") (pin "3") (pinfunction "VBAT_3") (pintype "power_in"))
      (node (ref "U4") (pin "1") (pinfunction "IN_1") (pintype "input"))
      (node (ref "U4") (pin "3") (pinfunction "EN_3") (pintype "input"))
    )
    (net (code "51") (name "VBUS") (class "Default")
      (node (ref "C1") (pin "1") (pinfunction "1_1") (pintype "passive"))
      (node (ref "RECHARGE") (pin "1") (pinfunction "1_1") (pintype "passive"))
      (node (ref "U1") (pin "4") (pinfunction "VIN_4") (pintype "power_in"))
    )
    (net (code "52") (name "VIBE_PWM") (class "Default")
      (node (ref "U$1") (pin "37") (pinfunction "PIO3_1/~{DSR}_37") (pintype "bidirectional"))
      (node (ref "U$3") (pin "+") (pinfunction "+_+") (pintype "bidirectional"))
    )
    (net (code "53") (name "XTALIN") (class "Default")
      (node (ref "C13") (pin "2") (pinfunction "2_2") (pintype "passive"))
      (node (ref "U$1") (pin "6") (pinfunction "XTALIN_6") (pintype "passive"))
      (node (ref "Y1") (pin "3") (pinfunction "2_3") (pintype "passive"))
    )
    (net (code "54") (name "XTALINB") (class "Default")
      (node (ref "C17") (pin "2") (pinfunction "2_2") (pintype "passive"))
      (node (ref "IC1") (pin "2") (pinfunction "XTAL1_2") (pintype "bidirectional"))
      (node (ref "Y2") (pin "3") (pinfunction "2_3") (pintype "passive"))
    )
    (net (code "55") (name "XTALOUT") (class "Default")
      (node (ref "C12") (pin "2") (pinfunction "2_2") (pintype "passive"))
      (node (ref "U$1") (pin "7") (pinfunction "XTALOUT_7") (pintype "passive"))
      (node (ref "Y1") (pin "1") (pinfunction "1_1") (pintype "passive"))
    )
    (net (code "56") (name "XTALOUTB") (class "Default")
      (node (ref "C16") (pin "2") (pinfunction "2_2") (pintype "passive"))
      (node (ref "IC1") (pin "3") (pinfunction "XTAL2_3") (pintype "bidirectional"))
      (node (ref "Y2") (pin "1") (pinfunction "1_1") (pintype "passive"))
    )
    (net (code "57") (name "unconnected-(ACCELEROMETER-NC-Pad3)") (class "Default")
      (node (ref "ACCELEROMETER") (pin "3") (pinfunction "NC_3") (pintype "bidirectional"))
    )
    (net (code "58") (name "unconnected-(ACCELEROMETER-NC-Pad10)") (class "Default")
      (node (ref "ACCELEROMETER") (pin "10") (pinfunction "NC_10") (pintype "bidirectional"))
    )
    (net (code "59") (name "unconnected-(ACCELEROMETER-NC-Pad11)") (class "Default")
      (node (ref "ACCELEROMETER") (pin "11") (pinfunction "NC_11") (pintype "bidirectional"))
    )
    (net (code "60") (name "unconnected-(IC1-A0-{slash}CS-Pad6)") (class "Default")
      (node (ref "IC1") (pin "6") (pinfunction "A0-/CS_6") (pintype "bidirectional"))
    )
    (net (code "61") (name "unconnected-(IC1-A1-SI-Pad7)") (class "Default")
      (node (ref "IC1") (pin "7") (pinfunction "A1-SI_7") (pintype "bidirectional"))
    )
    (net (code "62") (name "unconnected-(IC1-GPIO0-Pad12)") (class "Default")
      (node (ref "IC1") (pin "12") (pinfunction "GPIO0_12") (pintype "bidirectional"))
    )
    (net (code "63") (name "unconnected-(IC1-GPIO1-Pad13)") (class "Default")
      (node (ref "IC1") (pin "13") (pinfunction "GPIO1_13") (pintype "bidirectional"))
    )
    (net (code "64") (name "unconnected-(IC1-GPIO2-Pad14)") (class "Default")
      (node (ref "IC1") (pin "14") (pinfunction "GPIO2_14") (pintype "bidirectional"))
    )
    (net (code "65") (name "unconnected-(IC1-GPIO3-Pad15)") (class "Default")
      (node (ref "IC1") (pin "15") (pinfunction "GPIO3_15") (pintype "bidirectional"))
    )
    (net (code "66") (name "unconnected-(IC1-GPIO4-{slash}DSR-Pad17)") (class "Default")
      (node (ref "IC1") (pin "17") (pinfunction "GPIO4-/DSR_17") (pintype "bidirectional"))
    )
    (net (code "67") (name "unconnected-(IC1-GPIO5-{slash}DTR-Pad18)") (class "Default")
      (node (ref "IC1") (pin "18") (pinfunction "GPIO5-/DTR_18") (pintype "bidirectional"))
    )
    (net (code "68") (name "unconnected-(IC1-GPIO6-{slash}CD-Pad19)") (class "Default")
      (node (ref "IC1") (pin "19") (pinfunction "GPIO6-/CD_19") (pintype "bidirectional"))
    )
    (net (code "69") (name "unconnected-(IC1-GPIO7-{slash}RI-Pad20)") (class "Default")
      (node (ref "IC1") (pin "20") (pinfunction "GPIO7-/RI_20") (pintype "bidirectional"))
    )
    (net (code "70") (name "unconnected-(IC1-NC-SO-Pad8)") (class "Default")
      (node (ref "IC1") (pin "8") (pinfunction "NC-SO_8") (pintype "bidirectional"))
    )
    (net (code "71") (name "unconnected-(U$1-PIO0_1{slash}CLKOUT{slash}CT32B0_MAT2-Pad4)") (class "Default")
      (node (ref "U$1") (pin "4") (pinfunction "PIO0_1/CLKOUT/CT32B0_MAT2_4") (pintype "bidirectional"))
    )
    (net (code "72") (name "unconnected-(U$1-PIO0_2{slash}SSEL0{slash}CT16B0_CAP0-Pad10)") (class "Default")
      (node (ref "U$1") (pin "10") (pinfunction "PIO0_2/SSEL0/CT16B0_CAP0_10") (pintype "bidirectional"))
    )
    (net (code "73") (name "unconnected-(U$1-PIO0_3-Pad14)") (class "Default")
      (node (ref "U$1") (pin "14") (pinfunction "PIO0_3_14") (pintype "bidirectional"))
    )
    (net (code "74") (name "unconnected-(U$1-PIO0_6{slash}SCK0-Pad22)") (class "Default")
      (node (ref "U$1") (pin "22") (pinfunction "PIO0_6/SCK0_22") (pintype "bidirectional"))
    )
    (net (code "75") (name "unconnected-(U$1-PIO0_7{slash}~{CTS}-Pad23)") (class "Default")
      (node (ref "U$1") (pin "23") (pinfunction "PIO0_7/~{CTS}_23") (pintype "bidirectional"))
    )
    (net (code "76") (name "unconnected-(U$1-PIO0_8{slash}MISO0{slash}CT16B0_MAT0-Pad27)") (class "Default")
      (node (ref "U$1") (pin "27") (pinfunction "PIO0_8/MISO0/CT16B0_MAT0_27") (pintype "bidirectional"))
    )
    (net (code "77") (name "unconnected-(U$1-PIO1_4{slash}AD5{slash}CT32B1_MAT3{slash}WAKEUP-Pad40)") (class "Default")
      (node (ref "U$1") (pin "40") (pinfunction "PIO1_4/AD5/CT32B1_MAT3/WAKEUP_40") (pintype "bidirectional"))
    )
    (net (code "78") (name "unconnected-(U$1-PIO1_5{slash}~{RTS}{slash}CT32B0_CAP0-Pad45)") (class "Default")
      (node (ref "U$1") (pin "45") (pinfunction "PIO1_5/~{RTS}/CT32B0_CAP0_45") (pintype "bidirectional"))
    )
    (net (code "79") (name "unconnected-(U$1-PIO1_8{slash}CT16B1_CAP0-Pad9)") (class "Default")
      (node (ref "U$1") (pin "9") (pinfunction "PIO1_8/CT16B1_CAP0_9") (pintype "bidirectional"))
    )
    (net (code "80") (name "unconnected-(U$1-PIO1_9{slash}CT16B1_MAT0-Pad17)") (class "Default")
      (node (ref "U$1") (pin "17") (pinfunction "PIO1_9/CT16B1_MAT0_17") (pintype "bidirectional"))
    )
    (net (code "81") (name "unconnected-(U$1-PIO1_11{slash}AD7-Pad42)") (class "Default")
      (node (ref "U$1") (pin "42") (pinfunction "PIO1_11/AD7_42") (pintype "bidirectional"))
    )
    (net (code "82") (name "unconnected-(U$1-PIO2_0{slash}~{DTR}{slash}SSEL1-Pad2)") (class "Default")
      (node (ref "U$1") (pin "2") (pinfunction "PIO2_0/~{DTR}/SSEL1_2") (pintype "bidirectional"))
    )
    (net (code "83") (name "unconnected-(U$1-PIO2_1{slash}~{DSR}{slash}SCK1-Pad13)") (class "Default")
      (node (ref "U$1") (pin "13") (pinfunction "PIO2_1/~{DSR}/SCK1_13") (pintype "bidirectional"))
    )
    (net (code "84") (name "unconnected-(U$1-PIO2_2{slash}~{DCD}{slash}MISO1-Pad26)") (class "Default")
      (node (ref "U$1") (pin "26") (pinfunction "PIO2_2/~{DCD}/MISO1_26") (pintype "bidirectional"))
    )
    (net (code "85") (name "unconnected-(U$1-PIO2_3{slash}~{RI}{slash}MOSI1-Pad38)") (class "Default")
      (node (ref "U$1") (pin "38") (pinfunction "PIO2_3/~{RI}/MOSI1_38") (pintype "bidirectional"))
    )
    (net (code "86") (name "unconnected-(U$1-PIO2_4-Pad19)") (class "Default")
      (node (ref "U$1") (pin "19") (pinfunction "PIO2_4_19") (pintype "bidirectional"))
    )
    (net (code "87") (name "unconnected-(U$1-PIO2_5-Pad20)") (class "Default")
      (node (ref "U$1") (pin "20") (pinfunction "PIO2_5_20") (pintype "bidirectional"))
    )
    (net (code "88") (name "unconnected-(U$1-PIO2_6-Pad1)") (class "Default")
      (node (ref "U$1") (pin "1") (pinfunction "PIO2_6_1") (pintype "bidirectional"))
    )
    (net (code "89") (name "unconnected-(U$1-PIO2_7-Pad11)") (class "Default")
      (node (ref "U$1") (pin "11") (pinfunction "PIO2_7_11") (pintype "bidirectional"))
    )
    (net (code "90") (name "unconnected-(U$1-PIO2_8-Pad12)") (class "Default")
      (node (ref "U$1") (pin "12") (pinfunction "PIO2_8_12") (pintype "bidirectional"))
    )
    (net (code "91") (name "unconnected-(U$1-PIO2_9-Pad24)") (class "Default")
      (node (ref "U$1") (pin "24") (pinfunction "PIO2_9_24") (pintype "bidirectional"))
    )
    (net (code "92") (name "unconnected-(U$1-PIO2_10-Pad25)") (class "Default")
      (node (ref "U$1") (pin "25") (pinfunction "PIO2_10_25") (pintype "bidirectional"))
    )
    (net (code "93") (name "unconnected-(U$1-PIO3_2{slash}~{DCD}-Pad43)") (class "Default")
      (node (ref "U$1") (pin "43") (pinfunction "PIO3_2/~{DCD}_43") (pintype "bidirectional"))
    )
    (net (code "94") (name "unconnected-(U$1-PIO3_3{slash}~{RI}-Pad48)") (class "Default")
      (node (ref "U$1") (pin "48") (pinfunction "PIO3_3/~{RI}_48") (pintype "bidirectional"))
    )
    (net (code "95") (name "unconnected-(U$1-PIO3_4-Pad18)") (class "Default")
      (node (ref "U$1") (pin "18") (pinfunction "PIO3_4_18") (pintype "bidirectional"))
    )
    (net (code "96") (name "unconnected-(U$1-PIO3_5-Pad21)") (class "Default")
      (node (ref "U$1") (pin "21") (pinfunction "PIO3_5_21") (pintype "bidirectional"))
    )
    (net (code "97") (name "unconnected-(U$4-AIO1-Pad35)") (class "Default")
      (node (ref "U$4") (pin "35") (pinfunction "AIO1_35") (pintype "bidirectional"))
    )
    (net (code "98") (name "unconnected-(U$4-AIO2-Pad30)") (class "Default")
      (node (ref "U$4") (pin "30") (pinfunction "AIO2_30") (pintype "bidirectional"))
    )
    (net (code "99") (name "unconnected-(U$4-NC-Pad26)") (class "Default")
      (node (ref "U$4") (pin "26") (pinfunction "NC_26") (pintype "bidirectional"))
    )
    (net (code "100") (name "unconnected-(U$4-PCMCLK-Pad7)") (class "Default")
      (node (ref "U$4") (pin "7") (pinfunction "PCMCLK_7") (pintype "bidirectional"))
    )
    (net (code "101") (name "unconnected-(U$4-PCMIN-Pad9)") (class "Default")
      (node (ref "U$4") (pin "9") (pinfunction "PCMIN_9") (pintype "bidirectional"))
    )
    (net (code "102") (name "unconnected-(U$4-PCMOUT-Pad10)") (class "Default")
      (node (ref "U$4") (pin "10") (pinfunction "PCMOUT_10") (pintype "bidirectional"))
    )
    (net (code "103") (name "unconnected-(U$4-PCMSYNC-Pad8)") (class "Default")
      (node (ref "U$4") (pin "8") (pinfunction "PCMSYNC_8") (pintype "bidirectional"))
    )
    (net (code "104") (name "unconnected-(U$4-PIO3-Pad20)") (class "Default")
      (node (ref "U$4") (pin "20") (pinfunction "PIO3_20") (pintype "bidirectional"))
    )
    (net (code "105") (name "unconnected-(U$4-PIO6-Pad3)") (class "Default")
      (node (ref "U$4") (pin "3") (pinfunction "PIO6_3") (pintype "bidirectional"))
    )
    (net (code "106") (name "unconnected-(U$4-PIO7-Pad4)") (class "Default")
      (node (ref "U$4") (pin "4") (pinfunction "PIO7_4") (pintype "bidirectional"))
    )
    (net (code "107") (name "unconnected-(U$4-PIO8-Pad31)") (class "Default")
      (node (ref "U$4") (pin "31") (pinfunction "PIO8_31") (pintype "bidirectional"))
    )
    (net (code "108") (name "unconnected-(U$4-PIO9-Pad32)") (class "Default")
      (node (ref "U$4") (pin "32") (pinfunction "PIO9_32") (pintype "bidirectional"))
    )
    (net (code "109") (name "unconnected-(U$4-PIO10-Pad33)") (class "Default")
      (node (ref "U$4") (pin "33") (pinfunction "PIO10_33") (pintype "bidirectional"))
    )
    (net (code "110") (name "unconnected-(U$4-PIO11-Pad34)") (class "Default")
      (node (ref "U$4") (pin "34") (pinfunction "PIO11_34") (pintype "bidirectional"))
    )
    (net (code "111") (name "unconnected-(U$4-RESET-Pad5)") (class "Default")
      (node (ref "U$4") (pin "5") (pinfunction "RESET_5") (pintype "bidirectional"))
    )
    (net (code "112") (name "unconnected-(U$4-SPICLK-Pad6)") (class "Default")
      (node (ref "U$4") (pin "6") (pinfunction "SPICLK_6") (pintype "bidirectional"))
    )
    (net (code "113") (name "unconnected-(U$4-SPICSB-Pad23)") (class "Default")
      (node (ref "U$4") (pin "23") (pinfunction "SPICSB_23") (pintype "bidirectional"))
    )
    (net (code "114") (name "unconnected-(U$4-SPIMISO-Pad24)") (class "Default")
      (node (ref "U$4") (pin "24") (pinfunction "SPIMISO_24") (pintype "bidirectional"))
    )
    (net (code "115") (name "unconnected-(U$4-SPIMOSI-Pad2)") (class "Default")
      (node (ref "U$4") (pin "2") (pinfunction "SPIMOSI_2") (pintype "bidirectional"))
    )
    (net (code "116") (name "unconnected-(U$4-USBD+-Pad17)") (class "Default")
      (node (ref "U$4") (pin "17") (pinfunction "USBD+_17") (pintype "bidirectional"))
    )
    (net (code "117") (name "unconnected-(U$4-USBD--Pad18)") (class "Default")
      (node (ref "U$4") (pin "18") (pinfunction "USBD-_18") (pintype "bidirectional"))
    )
    (net (code "118") (name "unconnected-(U1-STAT-Pad1)") (class "Default")
      (node (ref "U1") (pin "1") (pinfunction "STAT_1") (pintype "output"))
    )
    (net (code "119") (name "unconnected-(U3-ALT-Pad5)") (class "Default")
      (node (ref "U3") (pin "5") (pinfunction "ALT_5") (pintype "bidirectional"))
    )
    (net (code "120") (name "unconnected-(U4-BP-Pad4)") (class "Default")
      (node (ref "U4") (pin "4") (pinfunction "BP_4") (pintype "input"))
    )
  )
)
